# main1-rev-b.net
KiCad netlist of a schematic drawn in EAGLE
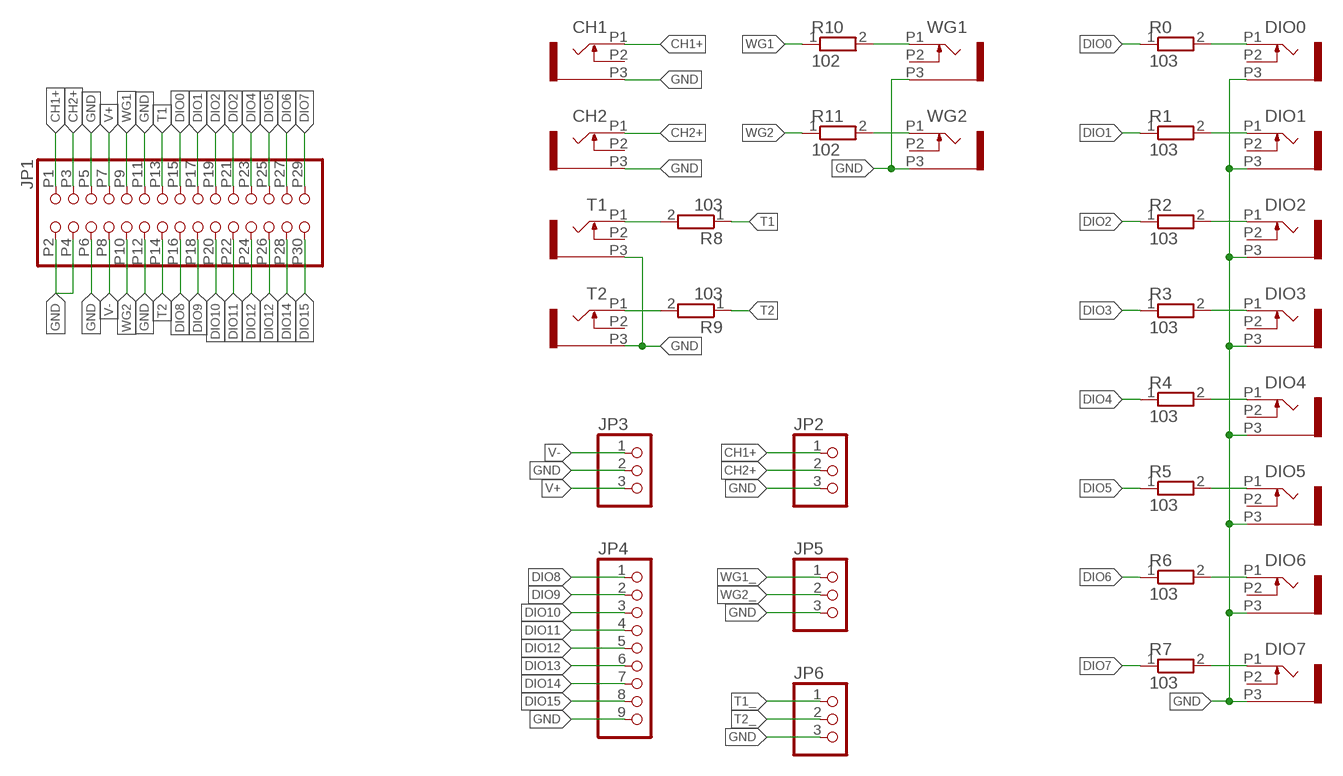
[diagram p0: schematic, sheet 1]

(export (version "E")
  (design (tool "Eeschema 10.0.6"))
  (components
    (comp (ref "CH1")
      (value "THONKICONN")
      (footprint "eagle-import:WQP-PJ301M-12_JACK")
      (libsource (lib "eagle-import") (part "THONKICONN"))
    )
    (comp (ref "CH2")
      (value "THONKICONN")
      (footprint "eagle-import:WQP-PJ301M-12_JACK")
      (libsource (lib "eagle-import") (part "THONKICONN"))
    )
    (comp (ref "DIO0")
      (value "THONKICONN")
      (footprint "eagle-import:WQP-PJ301M-12_JACK")
      (libsource (lib "eagle-import") (part "THONKICONN"))
    )
    (comp (ref "DIO1")
      (value "THONKICONN")
      (footprint "eagle-import:WQP-PJ301M-12_JACK")
      (libsource (lib "eagle-import") (part "THONKICONN"))
    )
    (comp (ref "DIO2")
      (value "THONKICONN")
      (footprint "eagle-import:WQP-PJ301M-12_JACK")
      (libsource (lib "eagle-import") (part "THONKICONN"))
    )
    (comp (ref "DIO3")
      (value "THONKICONN")
      (footprint "eagle-import:WQP-PJ301M-12_JACK")
      (libsource (lib "eagle-import") (part "THONKICONN"))
    )
    (comp (ref "DIO4")
      (value "THONKICONN")
      (footprint "eagle-import:WQP-PJ301M-12_JACK")
      (libsource (lib "eagle-import") (part "THONKICONN"))
    )
    (comp (ref "DIO5")
      (value "THONKICONN")
      (footprint "eagle-import:WQP-PJ301M-12_JACK")
      (libsource (lib "eagle-import") (part "THONKICONN"))
    )
    (comp (ref "DIO6")
      (value "THONKICONN")
      (footprint "eagle-import:WQP-PJ301M-12_JACK")
      (libsource (lib "eagle-import") (part "THONKICONN"))
    )
    (comp (ref "DIO7")
      (value "THONKICONN")
      (footprint "eagle-import:WQP-PJ301M-12_JACK")
      (libsource (lib "eagle-import") (part "THONKICONN"))
    )
    (comp (ref "JP1")
      (value "PINHD-2X15")
      (footprint "eagle-import:2X15_EDGE")
      (libsource (lib "eagle-import") (part "PINHD-2X15"))
    )
    (comp (ref "JP2")
      (value "PINHD-1X3/OCT")
      (footprint "eagle-import:1X03_OCT")
      (libsource (lib "eagle-import") (part "PINHD-1X3/OCT"))
    )
    (comp (ref "JP3")
      (value "PINHD-1X3/OCT")
      (footprint "eagle-import:1X03_OCT")
      (libsource (lib "eagle-import") (part "PINHD-1X3/OCT"))
    )
    (comp (ref "JP4")
      (value "PINHD-1X9/OCT")
      (footprint "eagle-import:1X09_OCT")
      (libsource (lib "eagle-import") (part "PINHD-1X9/OCT"))
    )
    (comp (ref "JP5")
      (value "PINHD-1X3/OCT")
      (footprint "eagle-import:1X03_OCT")
      (libsource (lib "eagle-import") (part "PINHD-1X3/OCT"))
    )
    (comp (ref "JP6")
      (value "PINHD-1X3/OCT")
      (footprint "eagle-import:1X03_OCT")
      (libsource (lib "eagle-import") (part "PINHD-1X3/OCT"))
    )
    (comp (ref "R0")
      (value "103")
      (footprint "eagle-import:R0603")
      (libsource (lib "eagle-import") (part "R-EU_R0603"))
    )
    (comp (ref "R1")
      (value "103")
      (footprint "eagle-import:R0603")
      (libsource (lib "eagle-import") (part "R-EU_R0603"))
    )
    (comp (ref "R2")
      (value "103")
      (footprint "eagle-import:R0603")
      (libsource (lib "eagle-import") (part "R-EU_R0603"))
    )
    (comp (ref "R3")
      (value "103")
      (footprint "eagle-import:R0603")
      (libsource (lib "eagle-import") (part "R-EU_R0603"))
    )
    (comp (ref "R4")
      (value "103")
      (footprint "eagle-import:R0603")
      (libsource (lib "eagle-import") (part "R-EU_R0603"))
    )
    (comp (ref "R5")
      (value "103")
      (footprint "eagle-import:R0603")
      (libsource (lib "eagle-import") (part "R-EU_R0603"))
    )
    (comp (ref "R6")
      (value "103")
      (footprint "eagle-import:R0603")
      (libsource (lib "eagle-import") (part "R-EU_R0603"))
    )
    (comp (ref "R7")
      (value "103")
      (footprint "eagle-import:R0603")
      (libsource (lib "eagle-import") (part "R-EU_R0603"))
    )
    (comp (ref "R8")
      (value "103")
      (footprint "eagle-import:R0603")
      (libsource (lib "eagle-import") (part "R-EU_R0603"))
    )
    (comp (ref "R9")
      (value "103")
      (footprint "eagle-import:R0603")
      (libsource (lib "eagle-import") (part "R-EU_R0603"))
    )
    (comp (ref "R10")
      (value "102")
      (footprint "eagle-import:R0603")
      (libsource (lib "eagle-import") (part "R-EU_R0603"))
    )
    (comp (ref "R11")
      (value "102")
      (footprint "eagle-import:R0603")
      (libsource (lib "eagle-import") (part "R-EU_R0603"))
    )
    (comp (ref "T1")
      (value "THONKICONN")
      (footprint "eagle-import:WQP-PJ301M-12_JACK")
      (libsource (lib "eagle-import") (part "THONKICONN"))
    )
    (comp (ref "T2")
      (value "THONKICONN")
      (footprint "eagle-import:WQP-PJ301M-12_JACK")
      (libsource (lib "eagle-import") (part "THONKICONN"))
    )
    (comp (ref "WG1")
      (value "THONKICONN")
      (footprint "eagle-import:WQP-PJ301M-12_JACK")
      (libsource (lib "eagle-import") (part "THONKICONN"))
    )
    (comp (ref "WG2")
      (value "THONKICONN")
      (footprint "eagle-import:WQP-PJ301M-12_JACK")
      (libsource (lib "eagle-import") (part "THONKICONN"))
    )
  )
  (nets
    (net (code "1") (name "CH1+") (class "Default")
      (node (ref "CH1") (pin "P1") (pinfunction "2_P1") (pintype "passive"))
      (node (ref "JP1") (pin "P1") (pinfunction "1_P1") (pintype "passive"))
      (node (ref "JP2") (pin "1") (pinfunction "1_1") (pintype "passive"))
    )
    (net (code "2") (name "CH2+") (class "Default")
      (node (ref "CH2") (pin "P1") (pinfunction "2_P1") (pintype "passive"))
      (node (ref "JP1") (pin "P3") (pinfunction "3_P3") (pintype "passive"))
      (node (ref "JP2") (pin "2") (pinfunction "2_2") (pintype "passive"))
    )
    (net (code "3") (name "DIO0") (class "Default")
      (node (ref "JP1") (pin "P15") (pinfunction "15_P15") (pintype "passive"))
      (node (ref "R0") (pin "1") (pinfunction "1_1") (pintype "passive"))
    )
    (net (code "4") (name "DIO1") (class "Default")
      (node (ref "JP1") (pin "P17") (pinfunction "17_P17") (pintype "passive"))
      (node (ref "R1") (pin "1") (pinfunction "1_1") (pintype "passive"))
    )
    (net (code "5") (name "DIO2") (class "Default")
      (node (ref "JP1") (pin "P19") (pinfunction "19_P19") (pintype "passive"))
      (node (ref "R2") (pin "1") (pinfunction "1_1") (pintype "passive"))
    )
    (net (code "6") (name "DIO3") (class "Default")
      (node (ref "JP1") (pin "P21") (pinfunction "21_P21") (pintype "passive"))
      (node (ref "R3") (pin "1") (pinfunction "1_1") (pintype "passive"))
    )
    (net (code "7") (name "DIO4") (class "Default")
      (node (ref "JP1") (pin "P23") (pinfunction "23_P23") (pintype "passive"))
      (node (ref "R4") (pin "1") (pinfunction "1_1") (pintype "passive"))
    )
    (net (code "8") (name "DIO5") (class "Default")
      (node (ref "JP1") (pin "P25") (pinfunction "25_P25") (pintype "passive"))
      (node (ref "R5") (pin "1") (pinfunction "1_1") (pintype "passive"))
    )
    (net (code "9") (name "DIO6") (class "Default")
      (node (ref "JP1") (pin "P27") (pinfunction "27_P27") (pintype "passive"))
      (node (ref "R6") (pin "1") (pinfunction "1_1") (pintype "passive"))
    )
    (net (code "10") (name "DIO7") (class "Default")
      (node (ref "JP1") (pin "P29") (pinfunction "29_P29") (pintype "passive"))
      (node (ref "R7") (pin "1") (pinfunction "1_1") (pintype "passive"))
    )
    (net (code "11") (name "DIO8") (class "Default")
      (node (ref "JP1") (pin "P16") (pinfunction "16_P16") (pintype "passive"))
      (node (ref "JP4") (pin "1") (pinfunction "1_1") (pintype "passive"))
    )
    (net (code "12") (name "DIO9") (class "Default")
      (node (ref "JP1") (pin "P18") (pinfunction "18_P18") (pintype "passive"))
      (node (ref "JP4") (pin "2") (pinfunction "2_2") (pintype "passive"))
    )
    (net (code "13") (name "DIO10") (class "Default")
      (node (ref "JP1") (pin "P20") (pinfunction "20_P20") (pintype "passive"))
      (node (ref "JP4") (pin "3") (pinfunction "3_3") (pintype "passive"))
    )
    (net (code "14") (name "DIO11") (class "Default")
      (node (ref "JP1") (pin "P22") (pinfunction "22_P22") (pintype "passive"))
      (node (ref "JP4") (pin "4") (pinfunction "4_4") (pintype "passive"))
    )
    (net (code "15") (name "DIO12") (class "Default")
      (node (ref "JP1") (pin "P24") (pinfunction "24_P24") (pintype "passive"))
      (node (ref "JP4") (pin "5") (pinfunction "5_5") (pintype "passive"))
    )
    (net (code "16") (name "DIO13") (class "Default")
      (node (ref "JP1") (pin "P26") (pinfunction "26_P26") (pintype "passive"))
      (node (ref "JP4") (pin "6") (pinfunction "6_6") (pintype "passive"))
    )
    (net (code "17") (name "DIO14") (class "Default")
      (node (ref "JP1") (pin "P28") (pinfunction "28_P28") (pintype "passive"))
      (node (ref "JP4") (pin "7") (pinfunction "7_7") (pintype "passive"))
    )
    (net (code "18") (name "DIO15") (class "Default")
      (node (ref "JP1") (pin "P30") (pinfunction "30_P30") (pintype "passive"))
      (node (ref "JP4") (pin "8") (pinfunction "8_8") (pintype "passive"))
    )
    (net (code "19") (name "GND") (class "Default")
      (node (ref "CH1") (pin "P3") (pinfunction "1_P3") (pintype "passive"))
      (node (ref "CH2") (pin "P3") (pinfunction "1_P3") (pintype "passive"))
      (node (ref "DIO0") (pin "P3") (pinfunction "1_P3") (pintype "passive"))
      (node (ref "DIO1") (pin "P3") (pinfunction "1_P3") (pintype "passive"))
      (node (ref "DIO2") (pin "P3") (pinfunction "1_P3") (pintype "passive"))
      (node (ref "DIO3") (pin "P3") (pinfunction "1_P3") (pintype "passive"))
      (node (ref "DIO4") (pin "P3") (pinfunction "1_P3") (pintype "passive"))
      (node (ref "DIO5") (pin "P3") (pinfunction "1_P3") (pintype "passive"))
      (node (ref "DIO6") (pin "P3") (pinfunction "1_P3") (pintype "passive"))
      (node (ref "DIO7") (pin "P3") (pinfunction "1_P3") (pintype "passive"))
      (node (ref "JP1") (pin "P11") (pinfunction "11_P11") (pintype "passive"))
      (node (ref "JP1") (pin "P12") (pinfunction "12_P12") (pintype "passive"))
      (node (ref "JP1") (pin "P2") (pinfunction "2_P2") (pintype "passive"))
      (node (ref "JP1") (pin "P4") (pinfunction "4_P4") (pintype "passive"))
      (node (ref "JP1") (pin "P5") (pinfunction "5_P5") (pintype "passive"))
      (node (ref "JP1") (pin "P6") (pinfunction "6_P6") (pintype "passive"))
      (node (ref "JP2") (pin "3") (pinfunction "3_3") (pintype "passive"))
      (node (ref "JP3") (pin "2") (pinfunction "2_2") (pintype "passive"))
      (node (ref "JP4") (pin "9") (pinfunction "9_9") (pintype "passive"))
      (node (ref "JP5") (pin "3") (pinfunction "3_3") (pintype "passive"))
      (node (ref "JP6") (pin "3") (pinfunction "3_3") (pintype "passive"))
      (node (ref "T1") (pin "P3") (pinfunction "1_P3") (pintype "passive"))
      (node (ref "T2") (pin "P3") (pinfunction "1_P3") (pintype "passive"))
      (node (ref "WG1") (pin "P3") (pinfunction "1_P3") (pintype "passive"))
      (node (ref "WG2") (pin "P3") (pinfunction "1_P3") (pintype "passive"))
    )
    (net (code "20") (name "Net-(DIO0-2)") (class "Default")
      (node (ref "DIO0") (pin "P1") (pinfunction "2_P1") (pintype "passive"))
      (node (ref "R0") (pin "2") (pinfunction "2_2") (pintype "passive"))
    )
    (net (code "21") (name "Net-(DIO1-2)") (class "Default")
      (node (ref "DIO1") (pin "P1") (pinfunction "2_P1") (pintype "passive"))
      (node (ref "R1") (pin "2") (pinfunction "2_2") (pintype "passive"))
    )
    (net (code "22") (name "Net-(DIO2-2)") (class "Default")
      (node (ref "DIO2") (pin "P1") (pinfunction "2_P1") (pintype "passive"))
      (node (ref "R2") (pin "2") (pinfunction "2_2") (pintype "passive"))
    )
    (net (code "23") (name "Net-(DIO3-2)") (class "Default")
      (node (ref "DIO3") (pin "P1") (pinfunction "2_P1") (pintype "passive"))
      (node (ref "R3") (pin "2") (pinfunction "2_2") (pintype "passive"))
    )
    (net (code "24") (name "Net-(DIO4-2)") (class "Default")
      (node (ref "DIO4") (pin "P1") (pinfunction "2_P1") (pintype "passive"))
      (node (ref "R4") (pin "2") (pinfunction "2_2") (pintype "passive"))
    )
    (net (code "25") (name "Net-(DIO5-2)") (class "Default")
      (node (ref "DIO5") (pin "P1") (pinfunction "2_P1") (pintype "passive"))
      (node (ref "R5") (pin "2") (pinfunction "2_2") (pintype "passive"))
    )
    (net (code "26") (name "Net-(DIO6-2)") (class "Default")
      (node (ref "DIO6") (pin "P1") (pinfunction "2_P1") (pintype "passive"))
      (node (ref "R6") (pin "2") (pinfunction "2_2") (pintype "passive"))
    )
    (net (code "27") (name "Net-(DIO7-2)") (class "Default")
      (node (ref "DIO7") (pin "P1") (pinfunction "2_P1") (pintype "passive"))
      (node (ref "R7") (pin "2") (pinfunction "2_2") (pintype "passive"))
    )
    (net (code "28") (name "T1") (class "Default")
      (node (ref "JP1") (pin "P13") (pinfunction "13_P13") (pintype "passive"))
      (node (ref "R8") (pin "1") (pinfunction "1_1") (pintype "passive"))
    )
    (net (code "29") (name "T1_") (class "Default")
      (node (ref "JP6") (pin "1") (pinfunction "1_1") (pintype "passive"))
      (node (ref "R8") (pin "2") (pinfunction "2_2") (pintype "passive"))
      (node (ref "T1") (pin "P1") (pinfunction "2_P1") (pintype "passive"))
    )
    (net (code "30") (name "T2") (class "Default")
      (node (ref "JP1") (pin "P14") (pinfunction "14_P14") (pintype "passive"))
      (node (ref "R9") (pin "1") (pinfunction "1_1") (pintype "passive"))
    )
    (net (code "31") (name "T2_") (class "Default")
      (node (ref "JP6") (pin "2") (pinfunction "2_2") (pintype "passive"))
      (node (ref "R9") (pin "2") (pinfunction "2_2") (pintype "passive"))
      (node (ref "T2") (pin "P1") (pinfunction "2_P1") (pintype "passive"))
    )
    (net (code "32") (name "V+") (class "Default")
      (node (ref "JP1") (pin "P7") (pinfunction "7_P7") (pintype "passive"))
      (node (ref "JP3") (pin "3") (pinfunction "3_3") (pintype "passive"))
    )
    (net (code "33") (name "V-") (class "Default")
      (node (ref "JP1") (pin "P8") (pinfunction "8_P8") (pintype "passive"))
      (node (ref "JP3") (pin "1") (pinfunction "1_1") (pintype "passive"))
    )
    (net (code "34") (name "WG1") (class "Default")
      (node (ref "JP1") (pin "P9") (pinfunction "9_P9") (pintype "passive"))
      (node (ref "R10") (pin "1") (pinfunction "1_1") (pintype "passive"))
    )
    (net (code "35") (name "WG1_") (class "Default")
      (node (ref "JP5") (pin "1") (pinfunction "1_1") (pintype "passive"))
      (node (ref "R10") (pin "2") (pinfunction "2_2") (pintype "passive"))
      (node (ref "WG1") (pin "P1") (pinfunction "2_P1") (pintype "passive"))
    )
    (net (code "36") (name "WG2") (class "Default")
      (node (ref "JP1") (pin "P10") (pinfunction "10_P10") (pintype "passive"))
      (node (ref "R11") (pin "1") (pinfunction "1_1") (pintype "passive"))
    )
    (net (code "37") (name "WG2_") (class "Default")
      (node (ref "JP5") (pin "2") (pinfunction "2_2") (pintype "passive"))
      (node (ref "R11") (pin "2") (pinfunction "2_2") (pintype "passive"))
      (node (ref "WG2") (pin "P1") (pinfunction "2_P1") (pintype "passive"))
    )
    (net (code "38") (name "unconnected-(CH1-3-PadP2)") (class "Default")
      (node (ref "CH1") (pin "P2") (pinfunction "3_P2") (pintype "passive"))
    )
    (net (code "39") (name "unconnected-(CH2-3-PadP2)") (class "Default")
      (node (ref "CH2") (pin "P2") (pinfunction "3_P2") (pintype "passive"))
    )
    (net (code "40") (name "unconnected-(DIO0-3-PadP2)") (class "Default")
      (node (ref "DIO0") (pin "P2") (pinfunction "3_P2") (pintype "passive"))
    )
    (net (code "41") (name "unconnected-(DIO1-3-PadP2)") (class "Default")
      (node (ref "DIO1") (pin "P2") (pinfunction "3_P2") (pintype "passive"))
    )
    (net (code "42") (name "unconnected-(DIO2-3-PadP2)") (class "Default")
      (node (ref "DIO2") (pin "P2") (pinfunction "3_P2") (pintype "passive"))
    )
    (net (code "43") (name "unconnected-(DIO3-3-PadP2)") (class "Default")
      (node (ref "DIO3") (pin "P2") (pinfunction "3_P2") (pintype "passive"))
    )
    (net (code "44") (name "unconnected-(DIO4-3-PadP2)") (class "Default")
      (node (ref "DIO4") (pin "P2") (pinfunction "3_P2") (pintype "passive"))
    )
    (net (code "45") (name "unconnected-(DIO5-3-PadP2)") (class "Default")
      (node (ref "DIO5") (pin "P2") (pinfunction "3_P2") (pintype "passive"))
    )
    (net (code "46") (name "unconnected-(DIO6-3-PadP2)") (class "Default")
      (node (ref "DIO6") (pin "P2") (pinfunction "3_P2") (pintype "passive"))
    )
    (net (code "47") (name "unconnected-(DIO7-3-PadP2)") (class "Default")
      (node (ref "DIO7") (pin "P2") (pinfunction "3_P2") (pintype "passive"))
    )
    (net (code "48") (name "unconnected-(T1-3-PadP2)") (class "Default")
      (node (ref "T1") (pin "P2") (pinfunction "3_P2") (pintype "passive"))
    )
    (net (code "49") (name "unconnected-(T2-3-PadP2)") (class "Default")
      (node (ref "T2") (pin "P2") (pinfunction "3_P2") (pintype "passive"))
    )
    (net (code "50") (name "unconnected-(WG1-3-PadP2)") (class "Default")
      (node (ref "WG1") (pin "P2") (pinfunction "3_P2") (pintype "passive"))
    )
    (net (code "51") (name "unconnected-(WG2-3-PadP2)") (class "Default")
      (node (ref "WG2") (pin "P2") (pinfunction "3_P2") (pintype "passive"))
    )
  )
)
